# ALLPRINT-CAPBOARD-677512-INDEX-INPUTS.net
KiCad netlist of a schematic drawn in Altium Designer
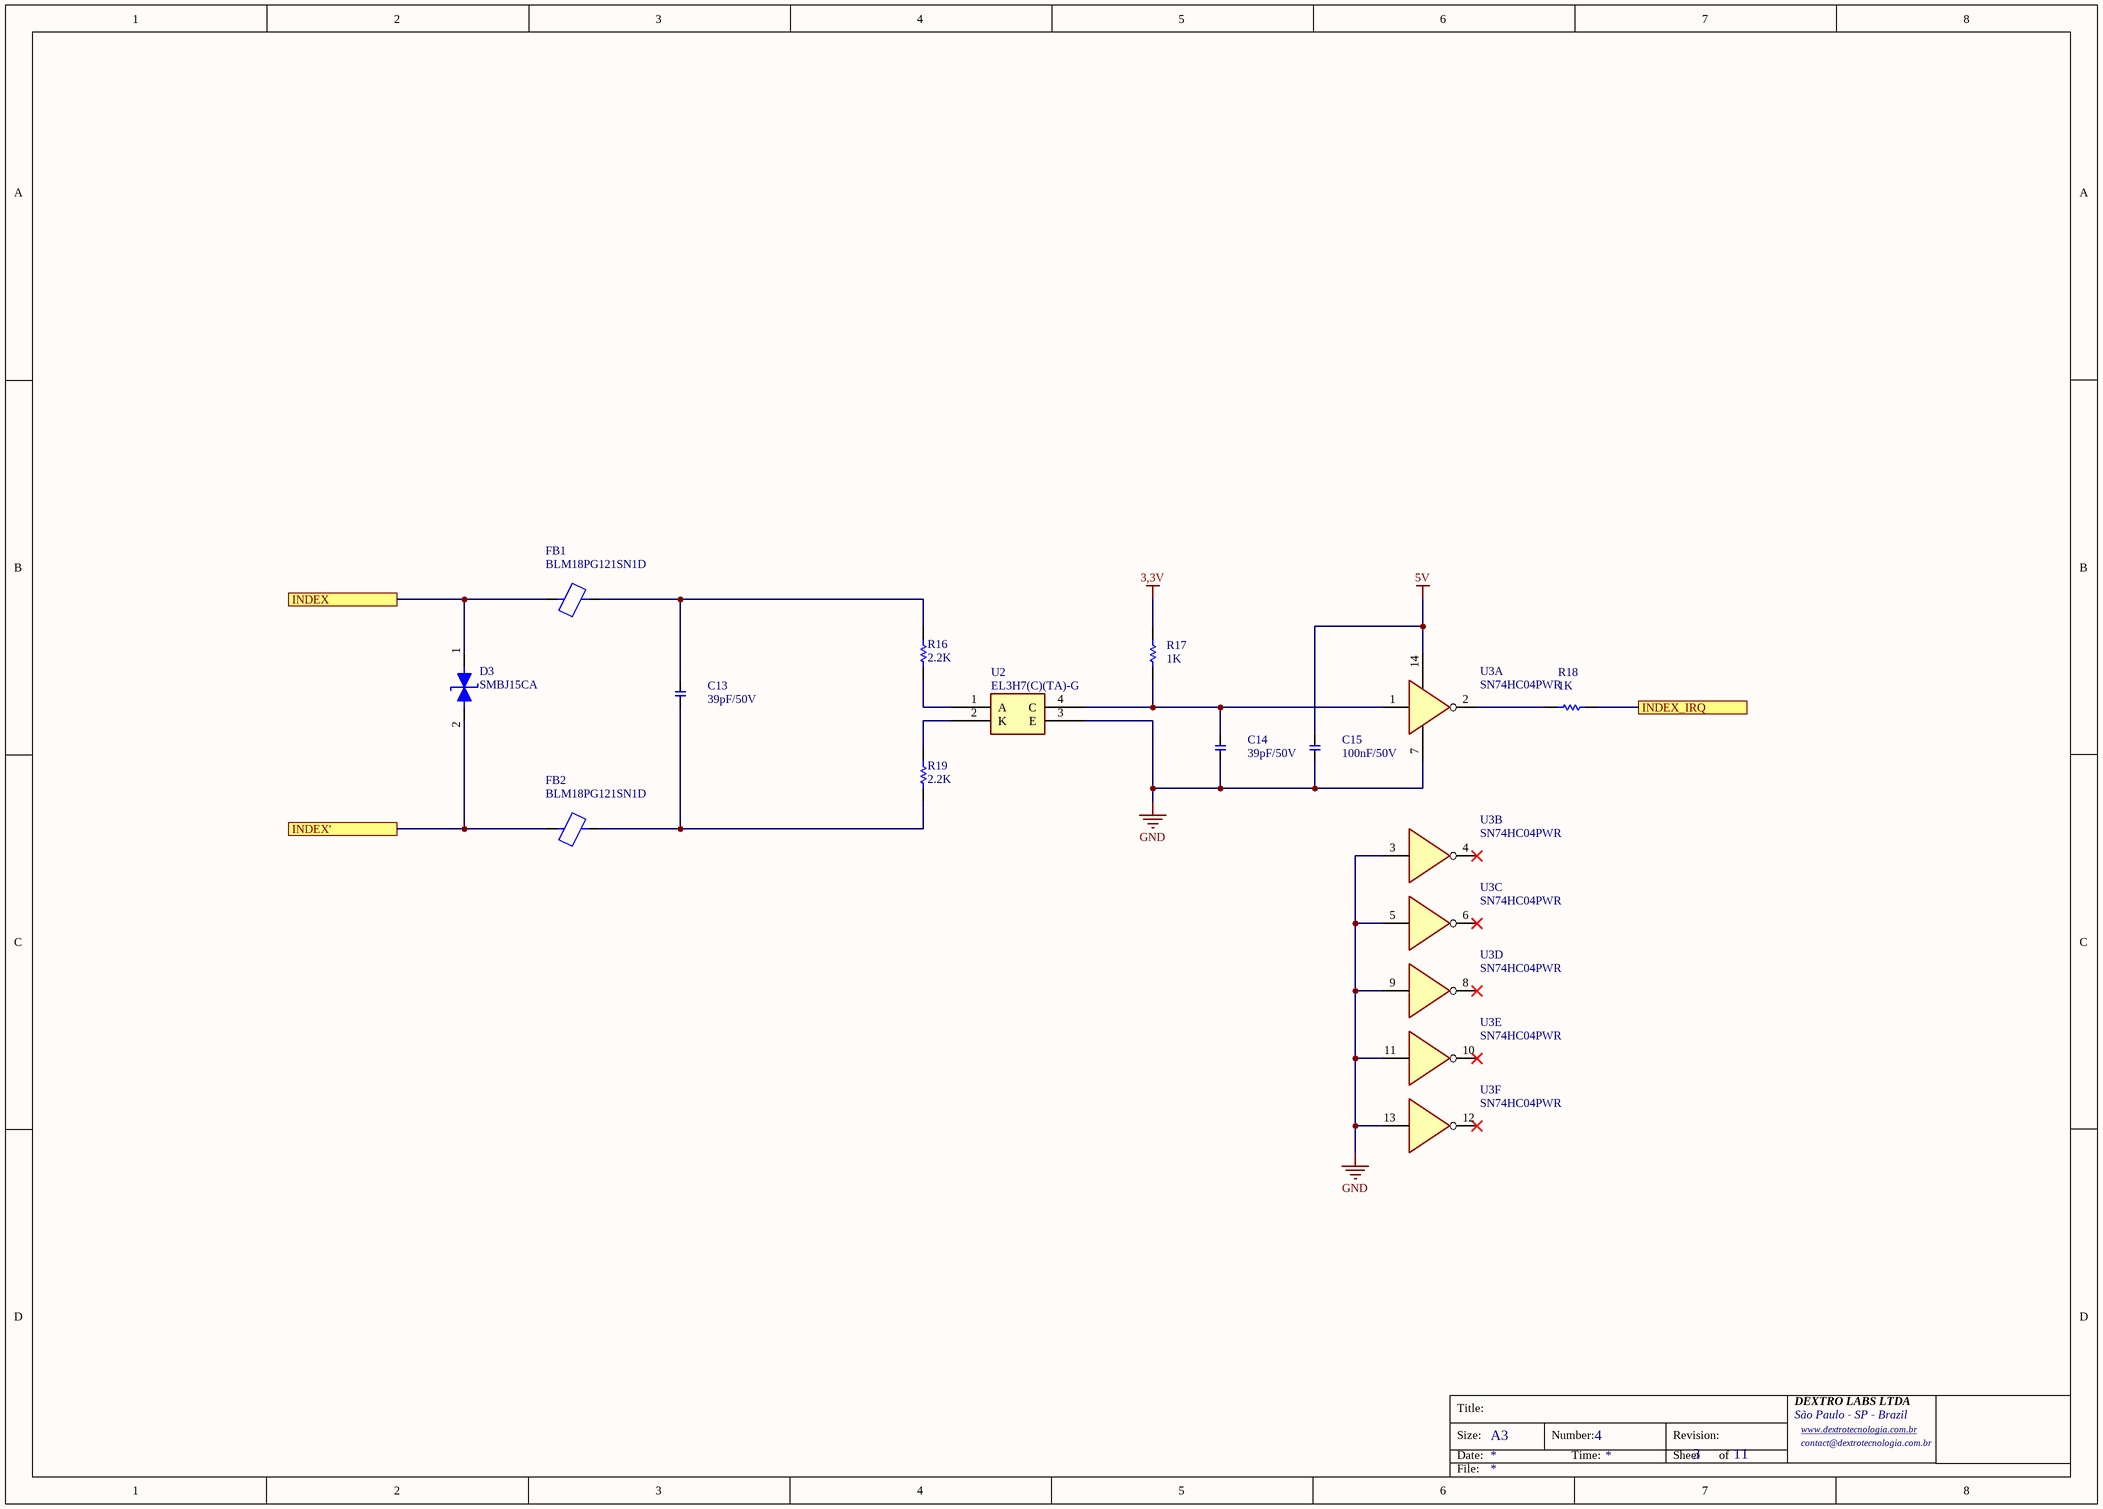
[diagram p0: ALLPRINT-CAPBOARD-677512-INDEX-INPUTS.SchDoc]

(export (version "E")
  (design (tool "Eeschema 10.0.6"))
  (components
    (comp (ref "C13")
      (value "39pF/50V")
      (footprint "CAP-0603")
      (description "50V 39pF X7R ±10% 0603 Multilayer Ceramic Capacitors MLCC - SMD/SMT ROHS")
      (libsource (lib "dextro-labs") (part "CAP-39pF/50V-0603-X7R-MLCC"))
    )
    (comp (ref "C14")
      (value "39pF/50V")
      (footprint "CAP-0603")
      (description "50V 39pF X7R ±10% 0603 Multilayer Ceramic Capacitors MLCC - SMD/SMT ROHS")
      (libsource (lib "dextro-labs") (part "CAP-39pF/50V-0603-X7R-MLCC"))
    )
    (comp (ref "C15")
      (value "100nF/50V")
      (footprint "CAP-0603")
      (description "50V 100nF X7R ±10% 0603 Multilayer Ceramic Capacitors MLCC - SMD/SMT ROHS")
      (libsource (lib "dextro-labs") (part "CAP-100nF/50V-0603-X7R-MLCC"))
    )
    (comp (ref "D3")
      (value "SMBJ15CA")
      (footprint "DO214-AA")
      (libsource (lib "dextro-labs") (part "SMBJ15CA"))
    )
    (comp (ref "FB1")
      (value "BLM18PG121SN1D")
      (footprint "RES-0603")
      (description "FERRITE BEAD 120Ω 0603 1LN")
      (libsource (lib "dextro-labs") (part "BLM18PG121SN1D"))
    )
    (comp (ref "FB2")
      (value "BLM18PG121SN1D")
      (footprint "RES-0603")
      (description "FERRITE BEAD 120Ω 0603 1LN")
      (libsource (lib "dextro-labs") (part "BLM18PG121SN1D"))
    )
    (comp (ref "R16")
      (value "2.2K")
      (footprint "RES-0805")
      (description "125mW 2.2kΩ 150V ±100ppm/℃ Thick Film Resistor ±1% 0805 Chip Resistor - Surface Mount ROHS")
      (libsource (lib "dextro-labs") (part "RES-2.2K-1%-125mW-0805"))
    )
    (comp (ref "R17")
      (value "1K")
      (footprint "RES-0805")
      (description "125mW Thick Film Resistor 150V ±100ppm/℃ ±1% 1kΩ 0805 Chip Resistor - Surface Mount ROHS")
      (libsource (lib "dextro-labs") (part "RES-1K-1%-125mW-0805"))
    )
    (comp (ref "R18")
      (value "1K")
      (footprint "RES-0805")
      (description "125mW Thick Film Resistor 150V ±100ppm/℃ ±1% 1kΩ 0805 Chip Resistor - Surface Mount ROHS")
      (libsource (lib "dextro-labs") (part "RES-1K-1%-125mW-0805"))
    )
    (comp (ref "R19")
      (value "2.2K")
      (footprint "RES-0805")
      (description "125mW 2.2kΩ 150V ±100ppm/℃ Thick Film Resistor ±1% 0805 Chip Resistor - Surface Mount ROHS")
      (libsource (lib "dextro-labs") (part "RES-2.2K-1%-125mW-0805"))
    )
    (comp (ref "U2")
      (value "EL3H7(C)(TA)-G")
      (footprint "SSOP-4")
      (libsource (lib "dextro-labs") (part "EL3H7(C)(TA)-G"))
    )
    (comp (ref "U3")
      (value "SN74HC04PWR")
      (footprint "TSSOP-14")
      (description "2V~6V 16ns@6V,50pF 2uA 6 1 TSSOP-14 Gates and Inverters RoHS")
      (libsource (lib "dextro-labs") (part "SN74HC04PWR"))
    )
  )
  (nets
    (net (code "1") (name "/INDEX") (class "Default")
      (node (ref "D3") (pin "1") (pinfunction "A1_1") (pintype "passive"))
      (node (ref "FB1") (pin "1") (pinfunction "1_1") (pintype "passive"))
    )
    (net (code "2") (name "/INDEX'") (class "Default")
      (node (ref "D3") (pin "2") (pinfunction "A2_2") (pintype "passive"))
      (node (ref "FB2") (pin "1") (pinfunction "1_1") (pintype "passive"))
    )
    (net (code "3") (name "/INDEX_IRQ") (class "Default")
      (node (ref "R18") (pin "2") (pinfunction "2_2") (pintype "passive"))
    )
    (net (code "4") (name "3,3V") (class "Default")
      (node (ref "R17") (pin "2") (pinfunction "2_2") (pintype "passive"))
    )
    (net (code "5") (name "5V") (class "Default")
      (node (ref "C15") (pin "2") (pinfunction "2_2") (pintype "passive"))
      (node (ref "U3") (pin "14") (pinfunction "VCC_14") (pintype "passive"))
    )
    (net (code "6") (name "GND") (class "Default")
      (node (ref "C14") (pin "1") (pinfunction "1_1") (pintype "passive"))
      (node (ref "C15") (pin "1") (pinfunction "1_1") (pintype "passive"))
      (node (ref "U2") (pin "3") (pinfunction "E_3") (pintype "passive"))
      (node (ref "U3") (pin "11") (pinfunction "11_11") (pintype "passive"))
      (node (ref "U3") (pin "13") (pinfunction "13_13") (pintype "passive"))
      (node (ref "U3") (pin "3") (pinfunction "4A_3") (pintype "passive"))
      (node (ref "U3") (pin "5") (pinfunction "5_5") (pintype "passive"))
      (node (ref "U3") (pin "7") (pinfunction "GND_7") (pintype "passive"))
      (node (ref "U3") (pin "9") (pinfunction "9_9") (pintype "passive"))
    )
    (net (code "7") (name "Net-(C13-Pad1)") (class "Default")
      (node (ref "C13") (pin "1") (pinfunction "1_1") (pintype "passive"))
      (node (ref "FB2") (pin "2") (pinfunction "2_2") (pintype "passive"))
      (node (ref "R19") (pin "1") (pinfunction "1_1") (pintype "passive"))
    )
    (net (code "8") (name "Net-(C13-Pad2)") (class "Default")
      (node (ref "C13") (pin "2") (pinfunction "2_2") (pintype "passive"))
      (node (ref "FB1") (pin "2") (pinfunction "2_2") (pintype "passive"))
      (node (ref "R16") (pin "2") (pinfunction "2_2") (pintype "passive"))
    )
    (net (code "9") (name "Net-(R18-Pad1)") (class "Default")
      (node (ref "R18") (pin "1") (pinfunction "1_1") (pintype "passive"))
      (node (ref "U3") (pin "2") (pinfunction "2_2") (pintype "passive"))
    )
    (net (code "10") (name "Net-(U2-A)") (class "Default")
      (node (ref "R16") (pin "1") (pinfunction "1_1") (pintype "passive"))
      (node (ref "U2") (pin "1") (pinfunction "A_1") (pintype "passive"))
    )
    (net (code "11") (name "Net-(U2-C)") (class "Default")
      (node (ref "C14") (pin "2") (pinfunction "2_2") (pintype "passive"))
      (node (ref "R17") (pin "1") (pinfunction "1_1") (pintype "passive"))
      (node (ref "U2") (pin "4") (pinfunction "C_4") (pintype "passive"))
      (node (ref "U3") (pin "1") (pinfunction "1A_1") (pintype "passive"))
    )
    (net (code "12") (name "Net-(U2-K)") (class "Default")
      (node (ref "R19") (pin "2") (pinfunction "2_2") (pintype "passive"))
      (node (ref "U2") (pin "2") (pinfunction "K_2") (pintype "passive"))
    )
    (net (code "13") (name "unconnected-(U3-Pad6)") (class "Default")
      (node (ref "U3") (pin "6") (pinfunction "6_6") (pintype "passive+no_connect"))
    )
    (net (code "14") (name "unconnected-(U3-Pad8)") (class "Default")
      (node (ref "U3") (pin "8") (pinfunction "8_8") (pintype "passive+no_connect"))
    )
    (net (code "15") (name "unconnected-(U3-Pad10)") (class "Default")
      (node (ref "U3") (pin "10") (pinfunction "10_10") (pintype "passive+no_connect"))
    )
    (net (code "16") (name "unconnected-(U3-Pad12)") (class "Default")
      (node (ref "U3") (pin "12") (pinfunction "12_12") (pintype "passive+no_connect"))
    )
    (net (code "17") (name "unconnected-(U3B-4Y-Pad4)") (class "Default")
      (node (ref "U3") (pin "4") (pinfunction "4Y_4") (pintype "passive+no_connect"))
    )
  )
)
